# DDR3_Power_Termination.net
KiCad netlist of a schematic drawn in Altium Designer
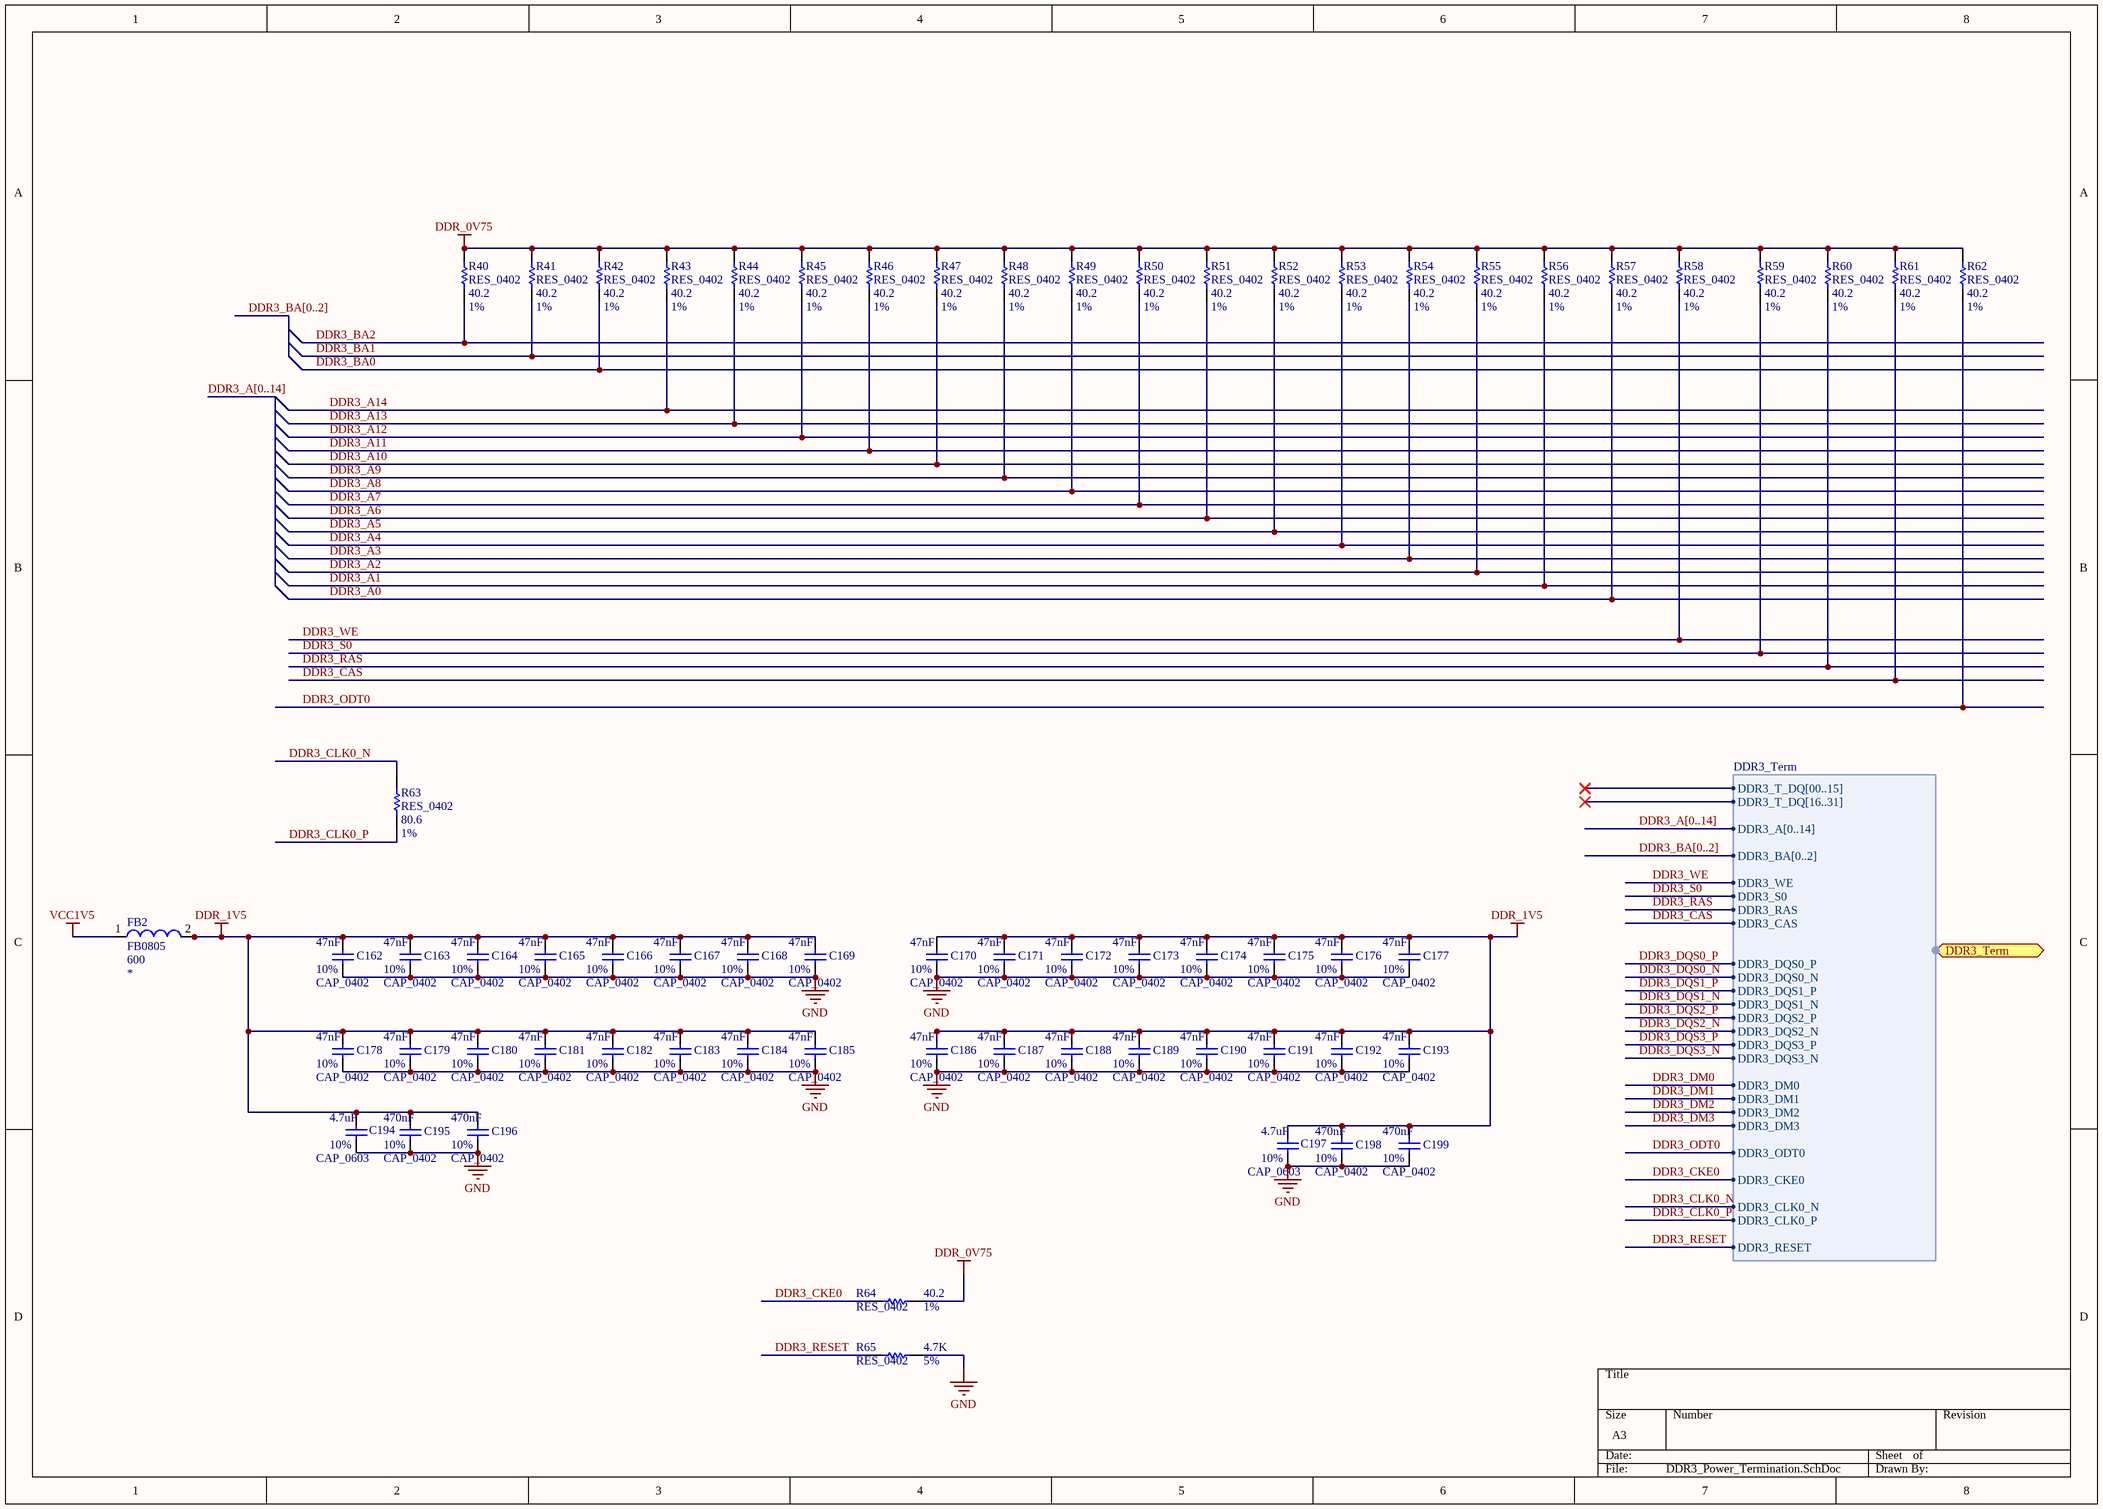
[diagram p0: DDR3_Power_Termination.SchDoc]

(export (version "E")
  (design (tool "Eeschema 10.0.6"))
  (components
    (comp (ref "C162")
      (value "CAP_0402")
      (footprint "CAPC0402(1005)60_N:CAPC0402(1005)60_N")
      (description "0.047uF, ceramic, 10% 6.3V X5R, 0402")
      (fields
        (field (name "ALTIUM_VALUE") "47nF")
        (field (name "TOLERANCE") "10%")
        (field (name "PART NUMBER") "GRM155R60J473KA01D")
        (field (name "MANUFACTURER") "Murata Electronics North America")
      )
      (libsource (lib "COMRAD_Database") (part "CAP_0402"))
    )
    (comp (ref "C163")
      (value "CAP_0402")
      (footprint "CAPC0402(1005)60_N:CAPC0402(1005)60_N")
      (description "0.047uF, ceramic, 10% 6.3V X5R, 0402")
      (fields
        (field (name "ALTIUM_VALUE") "47nF")
        (field (name "TOLERANCE") "10%")
        (field (name "PART NUMBER") "GRM155R60J473KA01D")
        (field (name "MANUFACTURER") "Murata Electronics North America")
      )
      (libsource (lib "COMRAD_Database") (part "CAP_0402"))
    )
    (comp (ref "C164")
      (value "CAP_0402")
      (footprint "CAPC0402(1005)60_N:CAPC0402(1005)60_N")
      (description "0.047uF, ceramic, 10% 6.3V X5R, 0402")
      (fields
        (field (name "ALTIUM_VALUE") "47nF")
        (field (name "TOLERANCE") "10%")
        (field (name "PART NUMBER") "GRM155R60J473KA01D")
        (field (name "MANUFACTURER") "Murata Electronics North America")
      )
      (libsource (lib "COMRAD_Database") (part "CAP_0402"))
    )
    (comp (ref "C165")
      (value "CAP_0402")
      (footprint "CAPC0402(1005)60_N:CAPC0402(1005)60_N")
      (description "0.047uF, ceramic, 10% 6.3V X5R, 0402")
      (fields
        (field (name "ALTIUM_VALUE") "47nF")
        (field (name "TOLERANCE") "10%")
        (field (name "PART NUMBER") "GRM155R60J473KA01D")
        (field (name "MANUFACTURER") "Murata Electronics North America")
      )
      (libsource (lib "COMRAD_Database") (part "CAP_0402"))
    )
    (comp (ref "C166")
      (value "CAP_0402")
      (footprint "CAPC0402(1005)60_N:CAPC0402(1005)60_N")
      (description "0.047uF, ceramic, 10% 6.3V X5R, 0402")
      (fields
        (field (name "ALTIUM_VALUE") "47nF")
        (field (name "TOLERANCE") "10%")
        (field (name "PART NUMBER") "GRM155R60J473KA01D")
        (field (name "MANUFACTURER") "Murata Electronics North America")
      )
      (libsource (lib "COMRAD_Database") (part "CAP_0402"))
    )
    (comp (ref "C167")
      (value "CAP_0402")
      (footprint "CAPC0402(1005)60_N:CAPC0402(1005)60_N")
      (description "0.047uF, ceramic, 10% 6.3V X5R, 0402")
      (fields
        (field (name "ALTIUM_VALUE") "47nF")
        (field (name "TOLERANCE") "10%")
        (field (name "PART NUMBER") "GRM155R60J473KA01D")
        (field (name "MANUFACTURER") "Murata Electronics North America")
      )
      (libsource (lib "COMRAD_Database") (part "CAP_0402"))
    )
    (comp (ref "C168")
      (value "CAP_0402")
      (footprint "CAPC0402(1005)60_N:CAPC0402(1005)60_N")
      (description "0.047uF, ceramic, 10% 6.3V X5R, 0402")
      (fields
        (field (name "ALTIUM_VALUE") "47nF")
        (field (name "TOLERANCE") "10%")
        (field (name "PART NUMBER") "GRM155R60J473KA01D")
        (field (name "MANUFACTURER") "Murata Electronics North America")
      )
      (libsource (lib "COMRAD_Database") (part "CAP_0402"))
    )
    (comp (ref "C169")
      (value "CAP_0402")
      (footprint "CAPC0402(1005)60_N:CAPC0402(1005)60_N")
      (description "0.047uF, ceramic, 10% 6.3V X5R, 0402")
      (fields
        (field (name "ALTIUM_VALUE") "47nF")
        (field (name "TOLERANCE") "10%")
        (field (name "PART NUMBER") "GRM155R60J473KA01D")
        (field (name "MANUFACTURER") "Murata Electronics North America")
      )
      (libsource (lib "COMRAD_Database") (part "CAP_0402"))
    )
    (comp (ref "C170")
      (value "CAP_0402")
      (footprint "CAPC0402(1005)60_N:CAPC0402(1005)60_N")
      (description "0.047uF, ceramic, 10% 6.3V X5R, 0402")
      (fields
        (field (name "ALTIUM_VALUE") "47nF")
        (field (name "TOLERANCE") "10%")
        (field (name "PART NUMBER") "GRM155R60J473KA01D")
        (field (name "MANUFACTURER") "Murata Electronics North America")
      )
      (libsource (lib "COMRAD_Database") (part "CAP_0402"))
    )
    (comp (ref "C171")
      (value "CAP_0402")
      (footprint "CAPC0402(1005)60_N:CAPC0402(1005)60_N")
      (description "0.047uF, ceramic, 10% 6.3V X5R, 0402")
      (fields
        (field (name "ALTIUM_VALUE") "47nF")
        (field (name "TOLERANCE") "10%")
        (field (name "PART NUMBER") "GRM155R60J473KA01D")
        (field (name "MANUFACTURER") "Murata Electronics North America")
      )
      (libsource (lib "COMRAD_Database") (part "CAP_0402"))
    )
    (comp (ref "C172")
      (value "CAP_0402")
      (footprint "CAPC0402(1005)60_N:CAPC0402(1005)60_N")
      (description "0.047uF, ceramic, 10% 6.3V X5R, 0402")
      (fields
        (field (name "ALTIUM_VALUE") "47nF")
        (field (name "TOLERANCE") "10%")
        (field (name "PART NUMBER") "GRM155R60J473KA01D")
        (field (name "MANUFACTURER") "Murata Electronics North America")
      )
      (libsource (lib "COMRAD_Database") (part "CAP_0402"))
    )
    (comp (ref "C173")
      (value "CAP_0402")
      (footprint "CAPC0402(1005)60_N:CAPC0402(1005)60_N")
      (description "0.047uF, ceramic, 10% 6.3V X5R, 0402")
      (fields
        (field (name "ALTIUM_VALUE") "47nF")
        (field (name "TOLERANCE") "10%")
        (field (name "PART NUMBER") "GRM155R60J473KA01D")
        (field (name "MANUFACTURER") "Murata Electronics North America")
      )
      (libsource (lib "COMRAD_Database") (part "CAP_0402"))
    )
    (comp (ref "C174")
      (value "CAP_0402")
      (footprint "CAPC0402(1005)60_N:CAPC0402(1005)60_N")
      (description "0.047uF, ceramic, 10% 6.3V X5R, 0402")
      (fields
        (field (name "ALTIUM_VALUE") "47nF")
        (field (name "TOLERANCE") "10%")
        (field (name "PART NUMBER") "GRM155R60J473KA01D")
        (field (name "MANUFACTURER") "Murata Electronics North America")
      )
      (libsource (lib "COMRAD_Database") (part "CAP_0402"))
    )
    (comp (ref "C175")
      (value "CAP_0402")
      (footprint "CAPC0402(1005)60_N:CAPC0402(1005)60_N")
      (description "0.047uF, ceramic, 10% 6.3V X5R, 0402")
      (fields
        (field (name "ALTIUM_VALUE") "47nF")
        (field (name "TOLERANCE") "10%")
        (field (name "PART NUMBER") "GRM155R60J473KA01D")
        (field (name "MANUFACTURER") "Murata Electronics North America")
      )
      (libsource (lib "COMRAD_Database") (part "CAP_0402"))
    )
    (comp (ref "C176")
      (value "CAP_0402")
      (footprint "CAPC0402(1005)60_N:CAPC0402(1005)60_N")
      (description "0.047uF, ceramic, 10% 6.3V X5R, 0402")
      (fields
        (field (name "ALTIUM_VALUE") "47nF")
        (field (name "TOLERANCE") "10%")
        (field (name "PART NUMBER") "GRM155R60J473KA01D")
        (field (name "MANUFACTURER") "Murata Electronics North America")
      )
      (libsource (lib "COMRAD_Database") (part "CAP_0402"))
    )
    (comp (ref "C177")
      (value "CAP_0402")
      (footprint "CAPC0402(1005)60_N:CAPC0402(1005)60_N")
      (description "0.047uF, ceramic, 10% 6.3V X5R, 0402")
      (fields
        (field (name "ALTIUM_VALUE") "47nF")
        (field (name "TOLERANCE") "10%")
        (field (name "PART NUMBER") "GRM155R60J473KA01D")
        (field (name "MANUFACTURER") "Murata Electronics North America")
      )
      (libsource (lib "COMRAD_Database") (part "CAP_0402"))
    )
    (comp (ref "C178")
      (value "CAP_0402")
      (footprint "CAPC0402(1005)60_N:CAPC0402(1005)60_N")
      (description "0.047uF, ceramic, 10% 6.3V X5R, 0402")
      (fields
        (field (name "ALTIUM_VALUE") "47nF")
        (field (name "TOLERANCE") "10%")
        (field (name "PART NUMBER") "GRM155R60J473KA01D")
        (field (name "MANUFACTURER") "Murata Electronics North America")
      )
      (libsource (lib "COMRAD_Database") (part "CAP_0402"))
    )
    (comp (ref "C179")
      (value "CAP_0402")
      (footprint "CAPC0402(1005)60_N:CAPC0402(1005)60_N")
      (description "0.047uF, ceramic, 10% 6.3V X5R, 0402")
      (fields
        (field (name "ALTIUM_VALUE") "47nF")
        (field (name "TOLERANCE") "10%")
        (field (name "PART NUMBER") "GRM155R60J473KA01D")
        (field (name "MANUFACTURER") "Murata Electronics North America")
      )
      (libsource (lib "COMRAD_Database") (part "CAP_0402"))
    )
    (comp (ref "C180")
      (value "CAP_0402")
      (footprint "CAPC0402(1005)60_N:CAPC0402(1005)60_N")
      (description "0.047uF, ceramic, 10% 6.3V X5R, 0402")
      (fields
        (field (name "ALTIUM_VALUE") "47nF")
        (field (name "TOLERANCE") "10%")
        (field (name "PART NUMBER") "GRM155R60J473KA01D")
        (field (name "MANUFACTURER") "Murata Electronics North America")
      )
      (libsource (lib "COMRAD_Database") (part "CAP_0402"))
    )
    (comp (ref "C181")
      (value "CAP_0402")
      (footprint "CAPC0402(1005)60_N:CAPC0402(1005)60_N")
      (description "0.047uF, ceramic, 10% 6.3V X5R, 0402")
      (fields
        (field (name "ALTIUM_VALUE") "47nF")
        (field (name "TOLERANCE") "10%")
        (field (name "PART NUMBER") "GRM155R60J473KA01D")
        (field (name "MANUFACTURER") "Murata Electronics North America")
      )
      (libsource (lib "COMRAD_Database") (part "CAP_0402"))
    )
    (comp (ref "C182")
      (value "CAP_0402")
      (footprint "CAPC0402(1005)60_N:CAPC0402(1005)60_N")
      (description "0.047uF, ceramic, 10% 6.3V X5R, 0402")
      (fields
        (field (name "ALTIUM_VALUE") "47nF")
        (field (name "TOLERANCE") "10%")
        (field (name "PART NUMBER") "GRM155R60J473KA01D")
        (field (name "MANUFACTURER") "Murata Electronics North America")
      )
      (libsource (lib "COMRAD_Database") (part "CAP_0402"))
    )
    (comp (ref "C183")
      (value "CAP_0402")
      (footprint "CAPC0402(1005)60_N:CAPC0402(1005)60_N")
      (description "0.047uF, ceramic, 10% 6.3V X5R, 0402")
      (fields
        (field (name "ALTIUM_VALUE") "47nF")
        (field (name "TOLERANCE") "10%")
        (field (name "PART NUMBER") "GRM155R60J473KA01D")
        (field (name "MANUFACTURER") "Murata Electronics North America")
      )
      (libsource (lib "COMRAD_Database") (part "CAP_0402"))
    )
    (comp (ref "C184")
      (value "CAP_0402")
      (footprint "CAPC0402(1005)60_N:CAPC0402(1005)60_N")
      (description "0.047uF, ceramic, 10% 6.3V X5R, 0402")
      (fields
        (field (name "ALTIUM_VALUE") "47nF")
        (field (name "TOLERANCE") "10%")
        (field (name "PART NUMBER") "GRM155R60J473KA01D")
        (field (name "MANUFACTURER") "Murata Electronics North America")
      )
      (libsource (lib "COMRAD_Database") (part "CAP_0402"))
    )
    (comp (ref "C185")
      (value "CAP_0402")
      (footprint "CAPC0402(1005)60_N:CAPC0402(1005)60_N")
      (description "0.047uF, ceramic, 10% 6.3V X5R, 0402")
      (fields
        (field (name "ALTIUM_VALUE") "47nF")
        (field (name "TOLERANCE") "10%")
        (field (name "PART NUMBER") "GRM155R60J473KA01D")
        (field (name "MANUFACTURER") "Murata Electronics North America")
      )
      (libsource (lib "COMRAD_Database") (part "CAP_0402"))
    )
    (comp (ref "C186")
      (value "CAP_0402")
      (footprint "CAPC0402(1005)60_N:CAPC0402(1005)60_N")
      (description "0.047uF, ceramic, 10% 6.3V X5R, 0402")
      (fields
        (field (name "ALTIUM_VALUE") "47nF")
        (field (name "TOLERANCE") "10%")
        (field (name "PART NUMBER") "GRM155R60J473KA01D")
        (field (name "MANUFACTURER") "Murata Electronics North America")
      )
      (libsource (lib "COMRAD_Database") (part "CAP_0402"))
    )
    (comp (ref "C187")
      (value "CAP_0402")
      (footprint "CAPC0402(1005)60_N:CAPC0402(1005)60_N")
      (description "0.047uF, ceramic, 10% 6.3V X5R, 0402")
      (fields
        (field (name "ALTIUM_VALUE") "47nF")
        (field (name "TOLERANCE") "10%")
        (field (name "PART NUMBER") "GRM155R60J473KA01D")
        (field (name "MANUFACTURER") "Murata Electronics North America")
      )
      (libsource (lib "COMRAD_Database") (part "CAP_0402"))
    )
    (comp (ref "C188")
      (value "CAP_0402")
      (footprint "CAPC0402(1005)60_N:CAPC0402(1005)60_N")
      (description "0.047uF, ceramic, 10% 6.3V X5R, 0402")
      (fields
        (field (name "ALTIUM_VALUE") "47nF")
        (field (name "TOLERANCE") "10%")
        (field (name "PART NUMBER") "GRM155R60J473KA01D")
        (field (name "MANUFACTURER") "Murata Electronics North America")
      )
      (libsource (lib "COMRAD_Database") (part "CAP_0402"))
    )
    (comp (ref "C189")
      (value "CAP_0402")
      (footprint "CAPC0402(1005)60_N:CAPC0402(1005)60_N")
      (description "0.047uF, ceramic, 10% 6.3V X5R, 0402")
      (fields
        (field (name "ALTIUM_VALUE") "47nF")
        (field (name "TOLERANCE") "10%")
        (field (name "PART NUMBER") "GRM155R60J473KA01D")
        (field (name "MANUFACTURER") "Murata Electronics North America")
      )
      (libsource (lib "COMRAD_Database") (part "CAP_0402"))
    )
    (comp (ref "C190")
      (value "CAP_0402")
      (footprint "CAPC0402(1005)60_N:CAPC0402(1005)60_N")
      (description "0.047uF, ceramic, 10% 6.3V X5R, 0402")
      (fields
        (field (name "ALTIUM_VALUE") "47nF")
        (field (name "TOLERANCE") "10%")
        (field (name "PART NUMBER") "GRM155R60J473KA01D")
        (field (name "MANUFACTURER") "Murata Electronics North America")
      )
      (libsource (lib "COMRAD_Database") (part "CAP_0402"))
    )
    (comp (ref "C191")
      (value "CAP_0402")
      (footprint "CAPC0402(1005)60_N:CAPC0402(1005)60_N")
      (description "0.047uF, ceramic, 10% 6.3V X5R, 0402")
      (fields
        (field (name "ALTIUM_VALUE") "47nF")
        (field (name "TOLERANCE") "10%")
        (field (name "PART NUMBER") "GRM155R60J473KA01D")
        (field (name "MANUFACTURER") "Murata Electronics North America")
      )
      (libsource (lib "COMRAD_Database") (part "CAP_0402"))
    )
    (comp (ref "C192")
      (value "CAP_0402")
      (footprint "CAPC0402(1005)60_N:CAPC0402(1005)60_N")
      (description "0.047uF, ceramic, 10% 6.3V X5R, 0402")
      (fields
        (field (name "ALTIUM_VALUE") "47nF")
        (field (name "TOLERANCE") "10%")
        (field (name "PART NUMBER") "GRM155R60J473KA01D")
        (field (name "MANUFACTURER") "Murata Electronics North America")
      )
      (libsource (lib "COMRAD_Database") (part "CAP_0402"))
    )
    (comp (ref "C193")
      (value "CAP_0402")
      (footprint "CAPC0402(1005)60_N:CAPC0402(1005)60_N")
      (description "0.047uF, ceramic, 10% 6.3V X5R, 0402")
      (fields
        (field (name "ALTIUM_VALUE") "47nF")
        (field (name "TOLERANCE") "10%")
        (field (name "PART NUMBER") "GRM155R60J473KA01D")
        (field (name "MANUFACTURER") "Murata Electronics North America")
      )
      (libsource (lib "COMRAD_Database") (part "CAP_0402"))
    )
    (comp (ref "C194")
      (value "CAP_0603")
      (footprint "CAPC0603(1608)100_N:CAPC0603(1608)100_N")
      (description "4.7uF, ceramic, 10% 6.3V X5R Low ESR, 0603")
      (fields
        (field (name "ALTIUM_VALUE") "4.7uF")
        (field (name "TOLERANCE") "10%")
        (field (name "PART NUMBER") "GRM188R60J475KE19D")
        (field (name "MANUFACTURER") "Murata Electronics North America")
      )
      (libsource (lib "COMRAD_Database") (part "CAP_0603"))
    )
    (comp (ref "C195")
      (value "CAP_0402")
      (footprint "CAPC0402(1005)60_N:CAPC0402(1005)60_N")
      (description "0.47uF, ceramic, 10% 6.3V X5R, 0402")
      (fields
        (field (name "ALTIUM_VALUE") "470nF")
        (field (name "TOLERANCE") "10%")
        (field (name "PART NUMBER") "GRM155R60J474KE19D")
        (field (name "MANUFACTURER") "Murata Electronics North America")
      )
      (libsource (lib "COMRAD_Database") (part "CAP_0402"))
    )
    (comp (ref "C196")
      (value "CAP_0402")
      (footprint "CAPC0402(1005)60_N:CAPC0402(1005)60_N")
      (description "0.47uF, ceramic, 10% 6.3V X5R, 0402")
      (fields
        (field (name "ALTIUM_VALUE") "470nF")
        (field (name "TOLERANCE") "10%")
        (field (name "PART NUMBER") "GRM155R60J474KE19D")
        (field (name "MANUFACTURER") "Murata Electronics North America")
      )
      (libsource (lib "COMRAD_Database") (part "CAP_0402"))
    )
    (comp (ref "C197")
      (value "CAP_0603")
      (footprint "CAPC0603(1608)100_N:CAPC0603(1608)100_N")
      (description "4.7uF, ceramic, 10% 6.3V X5R Low ESR, 0603")
      (fields
        (field (name "ALTIUM_VALUE") "4.7uF")
        (field (name "TOLERANCE") "10%")
        (field (name "PART NUMBER") "GRM188R60J475KE19D")
        (field (name "MANUFACTURER") "Murata Electronics North America")
      )
      (libsource (lib "COMRAD_Database") (part "CAP_0603"))
    )
    (comp (ref "C198")
      (value "CAP_0402")
      (footprint "CAPC0402(1005)60_N:CAPC0402(1005)60_N")
      (description "0.47uF, ceramic, 10% 6.3V X5R, 0402")
      (fields
        (field (name "ALTIUM_VALUE") "470nF")
        (field (name "TOLERANCE") "10%")
        (field (name "PART NUMBER") "GRM155R60J474KE19D")
        (field (name "MANUFACTURER") "Murata Electronics North America")
      )
      (libsource (lib "COMRAD_Database") (part "CAP_0402"))
    )
    (comp (ref "C199")
      (value "CAP_0402")
      (footprint "CAPC0402(1005)60_N:CAPC0402(1005)60_N")
      (description "0.47uF, ceramic, 10% 6.3V X5R, 0402")
      (fields
        (field (name "ALTIUM_VALUE") "470nF")
        (field (name "TOLERANCE") "10%")
        (field (name "PART NUMBER") "GRM155R60J474KE19D")
        (field (name "MANUFACTURER") "Murata Electronics North America")
      )
      (libsource (lib "COMRAD_Database") (part "CAP_0402"))
    )
    (comp (ref "FB2")
      (value "FB0805")
      (footprint "Inductor0805(2012)")
      (description "MPZ2012S601A, 600 ohm, 100MHz, 0805")
      (fields
        (field (name "RESISTANCE") "600")
        (field (name "MAX_CURRENT") "*")
        (field (name "PART NUMBER") "MPZ2012S601A")
        (field (name "MANUFACTURER") "TDK Corporation")
      )
      (libsource (lib "COMRAD_Database") (part "FerriteBead0805"))
    )
    (comp (ref "R40")
      (value "RES_0402")
      (footprint "RESC0402(1005)_N:RESC0402(1005)_N")
      (description "40.2 ohm, 1% 1/16W, 0402")
      (fields
        (field (name "ALTIUM_VALUE") "40.2")
        (field (name "TOLERANCE") "1%")
        (field (name "PART NUMBER") "RMCF0402FT40R2")
        (field (name "MANUFACTURER") "Stackpole Electronics")
      )
      (libsource (lib "COMRAD_Database") (part "RES_0402"))
    )
    (comp (ref "R41")
      (value "RES_0402")
      (footprint "RESC0402(1005)_N:RESC0402(1005)_N")
      (description "40.2 ohm, 1% 1/16W, 0402")
      (fields
        (field (name "ALTIUM_VALUE") "40.2")
        (field (name "TOLERANCE") "1%")
        (field (name "PART NUMBER") "RMCF0402FT40R2")
        (field (name "MANUFACTURER") "Stackpole Electronics")
      )
      (libsource (lib "COMRAD_Database") (part "RES_0402"))
    )
    (comp (ref "R42")
      (value "RES_0402")
      (footprint "RESC0402(1005)_N:RESC0402(1005)_N")
      (description "40.2 ohm, 1% 1/16W, 0402")
      (fields
        (field (name "ALTIUM_VALUE") "40.2")
        (field (name "TOLERANCE") "1%")
        (field (name "PART NUMBER") "RMCF0402FT40R2")
        (field (name "MANUFACTURER") "Stackpole Electronics")
      )
      (libsource (lib "COMRAD_Database") (part "RES_0402"))
    )
    (comp (ref "R43")
      (value "RES_0402")
      (footprint "RESC0402(1005)_N:RESC0402(1005)_N")
      (description "40.2 ohm, 1% 1/16W, 0402")
      (fields
        (field (name "ALTIUM_VALUE") "40.2")
        (field (name "TOLERANCE") "1%")
        (field (name "PART NUMBER") "RMCF0402FT40R2")
        (field (name "MANUFACTURER") "Stackpole Electronics")
      )
      (libsource (lib "COMRAD_Database") (part "RES_0402"))
    )
    (comp (ref "R44")
      (value "RES_0402")
      (footprint "RESC0402(1005)_N:RESC0402(1005)_N")
      (description "40.2 ohm, 1% 1/16W, 0402")
      (fields
        (field (name "ALTIUM_VALUE") "40.2")
        (field (name "TOLERANCE") "1%")
        (field (name "PART NUMBER") "RMCF0402FT40R2")
        (field (name "MANUFACTURER") "Stackpole Electronics")
      )
      (libsource (lib "COMRAD_Database") (part "RES_0402"))
    )
    (comp (ref "R45")
      (value "RES_0402")
      (footprint "RESC0402(1005)_N:RESC0402(1005)_N")
      (description "40.2 ohm, 1% 1/16W, 0402")
      (fields
        (field (name "ALTIUM_VALUE") "40.2")
        (field (name "TOLERANCE") "1%")
        (field (name "PART NUMBER") "RMCF0402FT40R2")
        (field (name "MANUFACTURER") "Stackpole Electronics")
      )
      (libsource (lib "COMRAD_Database") (part "RES_0402"))
    )
    (comp (ref "R46")
      (value "RES_0402")
      (footprint "RESC0402(1005)_N:RESC0402(1005)_N")
      (description "40.2 ohm, 1% 1/16W, 0402")
      (fields
        (field (name "ALTIUM_VALUE") "40.2")
        (field (name "TOLERANCE") "1%")
        (field (name "PART NUMBER") "RMCF0402FT40R2")
        (field (name "MANUFACTURER") "Stackpole Electronics")
      )
      (libsource (lib "COMRAD_Database") (part "RES_0402"))
    )
    (comp (ref "R47")
      (value "RES_0402")
      (footprint "RESC0402(1005)_N:RESC0402(1005)_N")
      (description "40.2 ohm, 1% 1/16W, 0402")
      (fields
        (field (name "ALTIUM_VALUE") "40.2")
        (field (name "TOLERANCE") "1%")
        (field (name "PART NUMBER") "RMCF0402FT40R2")
        (field (name "MANUFACTURER") "Stackpole Electronics")
      )
      (libsource (lib "COMRAD_Database") (part "RES_0402"))
    )
    (comp (ref "R48")
      (value "RES_0402")
      (footprint "RESC0402(1005)_N:RESC0402(1005)_N")
      (description "40.2 ohm, 1% 1/16W, 0402")
      (fields
        (field (name "ALTIUM_VALUE") "40.2")
        (field (name "TOLERANCE") "1%")
        (field (name "PART NUMBER") "RMCF0402FT40R2")
        (field (name "MANUFACTURER") "Stackpole Electronics")
      )
      (libsource (lib "COMRAD_Database") (part "RES_0402"))
    )
    (comp (ref "R49")
      (value "RES_0402")
      (footprint "RESC0402(1005)_N:RESC0402(1005)_N")
      (description "40.2 ohm, 1% 1/16W, 0402")
      (fields
        (field (name "ALTIUM_VALUE") "40.2")
        (field (name "TOLERANCE") "1%")
        (field (name "PART NUMBER") "RMCF0402FT40R2")
        (field (name "MANUFACTURER") "Stackpole Electronics")
      )
      (libsource (lib "COMRAD_Database") (part "RES_0402"))
    )
    (comp (ref "R50")
      (value "RES_0402")
      (footprint "RESC0402(1005)_N:RESC0402(1005)_N")
      (description "40.2 ohm, 1% 1/16W, 0402")
      (fields
        (field (name "ALTIUM_VALUE") "40.2")
        (field (name "TOLERANCE") "1%")
        (field (name "PART NUMBER") "RMCF0402FT40R2")
        (field (name "MANUFACTURER") "Stackpole Electronics")
      )
      (libsource (lib "COMRAD_Database") (part "RES_0402"))
    )
    (comp (ref "R51")
      (value "RES_0402")
      (footprint "RESC0402(1005)_N:RESC0402(1005)_N")
      (description "40.2 ohm, 1% 1/16W, 0402")
      (fields
        (field (name "ALTIUM_VALUE") "40.2")
        (field (name "TOLERANCE") "1%")
        (field (name "PART NUMBER") "RMCF0402FT40R2")
        (field (name "MANUFACTURER") "Stackpole Electronics")
      )
      (libsource (lib "COMRAD_Database") (part "RES_0402"))
    )
    (comp (ref "R52")
      (value "RES_0402")
      (footprint "RESC0402(1005)_N:RESC0402(1005)_N")
      (description "40.2 ohm, 1% 1/16W, 0402")
      (fields
        (field (name "ALTIUM_VALUE") "40.2")
        (field (name "TOLERANCE") "1%")
        (field (name "PART NUMBER") "RMCF0402FT40R2")
        (field (name "MANUFACTURER") "Stackpole Electronics")
      )
      (libsource (lib "COMRAD_Database") (part "RES_0402"))
    )
    (comp (ref "R53")
      (value "RES_0402")
      (footprint "RESC0402(1005)_N:RESC0402(1005)_N")
      (description "40.2 ohm, 1% 1/16W, 0402")
      (fields
        (field (name "ALTIUM_VALUE") "40.2")
        (field (name "TOLERANCE") "1%")
        (field (name "PART NUMBER") "RMCF0402FT40R2")
        (field (name "MANUFACTURER") "Stackpole Electronics")
      )
      (libsource (lib "COMRAD_Database") (part "RES_0402"))
    )
    (comp (ref "R54")
      (value "RES_0402")
      (footprint "RESC0402(1005)_N:RESC0402(1005)_N")
      (description "40.2 ohm, 1% 1/16W, 0402")
      (fields
        (field (name "ALTIUM_VALUE") "40.2")
        (field (name "TOLERANCE") "1%")
        (field (name "PART NUMBER") "RMCF0402FT40R2")
        (field (name "MANUFACTURER") "Stackpole Electronics")
      )
      (libsource (lib "COMRAD_Database") (part "RES_0402"))
    )
    (comp (ref "R55")
      (value "RES_0402")
      (footprint "RESC0402(1005)_N:RESC0402(1005)_N")
      (description "40.2 ohm, 1% 1/16W, 0402")
      (fields
        (field (name "ALTIUM_VALUE") "40.2")
        (field (name "TOLERANCE") "1%")
        (field (name "PART NUMBER") "RMCF0402FT40R2")
        (field (name "MANUFACTURER") "Stackpole Electronics")
      )
      (libsource (lib "COMRAD_Database") (part "RES_0402"))
    )
    (comp (ref "R56")
      (value "RES_0402")
      (footprint "RESC0402(1005)_N:RESC0402(1005)_N")
      (description "40.2 ohm, 1% 1/16W, 0402")
      (fields
        (field (name "ALTIUM_VALUE") "40.2")
        (field (name "TOLERANCE") "1%")
        (field (name "PART NUMBER") "RMCF0402FT40R2")
        (field (name "MANUFACTURER") "Stackpole Electronics")
      )
      (libsource (lib "COMRAD_Database") (part "RES_0402"))
    )
    (comp (ref "R57")
      (value "RES_0402")
      (footprint "RESC0402(1005)_N:RESC0402(1005)_N")
      (description "40.2 ohm, 1% 1/16W, 0402")
      (fields
        (field (name "ALTIUM_VALUE") "40.2")
        (field (name "TOLERANCE") "1%")
        (field (name "PART NUMBER") "RMCF0402FT40R2")
        (field (name "MANUFACTURER") "Stackpole Electronics")
      )
      (libsource (lib "COMRAD_Database") (part "RES_0402"))
    )
    (comp (ref "R58")
      (value "RES_0402")
      (footprint "RESC0402(1005)_N:RESC0402(1005)_N")
      (description "40.2 ohm, 1% 1/16W, 0402")
      (fields
        (field (name "ALTIUM_VALUE") "40.2")
        (field (name "TOLERANCE") "1%")
        (field (name "PART NUMBER") "RMCF0402FT40R2")
        (field (name "MANUFACTURER") "Stackpole Electronics")
      )
      (libsource (lib "COMRAD_Database") (part "RES_0402"))
    )
    (comp (ref "R59")
      (value "RES_0402")
      (footprint "RESC0402(1005)_N:RESC0402(1005)_N")
      (description "40.2 ohm, 1% 1/16W, 0402")
      (fields
        (field (name "ALTIUM_VALUE") "40.2")
        (field (name "TOLERANCE") "1%")
        (field (name "PART NUMBER") "RMCF0402FT40R2")
        (field (name "MANUFACTURER") "Stackpole Electronics")
      )
      (libsource (lib "COMRAD_Database") (part "RES_0402"))
    )
    (comp (ref "R60")
      (value "RES_0402")
      (footprint "RESC0402(1005)_N:RESC0402(1005)_N")
      (description "40.2 ohm, 1% 1/16W, 0402")
      (fields
        (field (name "ALTIUM_VALUE") "40.2")
        (field (name "TOLERANCE") "1%")
        (field (name "PART NUMBER") "RMCF0402FT40R2")
        (field (name "MANUFACTURER") "Stackpole Electronics")
      )
      (libsource (lib "COMRAD_Database") (part "RES_0402"))
    )
    (comp (ref "R61")
      (value "RES_0402")
      (footprint "RESC0402(1005)_N:RESC0402(1005)_N")
      (description "40.2 ohm, 1% 1/16W, 0402")
      (fields
        (field (name "ALTIUM_VALUE") "40.2")
        (field (name "TOLERANCE") "1%")
        (field (name "PART NUMBER") "RMCF0402FT40R2")
        (field (name "MANUFACTURER") "Stackpole Electronics")
      )
      (libsource (lib "COMRAD_Database") (part "RES_0402"))
    )
    (comp (ref "R62")
      (value "RES_0402")
      (footprint "RESC0402(1005)_N:RESC0402(1005)_N")
      (description "40.2 ohm, 1% 1/16W, 0402")
      (fields
        (field (name "ALTIUM_VALUE") "40.2")
        (field (name "TOLERANCE") "1%")
        (field (name "PART NUMBER") "RMCF0402FT40R2")
        (field (name "MANUFACTURER") "Stackpole Electronics")
      )
      (libsource (lib "COMRAD_Database") (part "RES_0402"))
    )
    (comp (ref "R63")
      (value "RES_0402")
      (footprint "RESC0402(1005)_N:RESC0402(1005)_N")
      (description "80.6 ohm, 1% 1/16W, 0402")
      (fields
        (field (name "ALTIUM_VALUE") "80.6")
        (field (name "TOLERANCE") "1%")
        (field (name "PART NUMBER") "RMCF0402FT80R6")
        (field (name "MANUFACTURER") "Stackpole Electronics")
      )
      (libsource (lib "COMRAD_Database") (part "RES_0402"))
    )
    (comp (ref "R64")
      (value "RES_0402")
      (footprint "RESC0402(1005)_N:RESC0402(1005)_N")
      (description "40.2 ohm, 1% 1/16W, 0402")
      (fields
        (field (name "ALTIUM_VALUE") "40.2")
        (field (name "TOLERANCE") "1%")
        (field (name "PART NUMBER") "RMCF0402FT40R2")
        (field (name "MANUFACTURER") "Stackpole Electronics")
      )
      (libsource (lib "COMRAD_Database") (part "RES_0402"))
    )
    (comp (ref "R65")
      (value "RES_0402")
      (footprint "RESC0402(1005)_N:RESC0402(1005)_N")
      (description "4.7K ohm, 5%, 1/16W, 0402")
      (fields
        (field (name "ALTIUM_VALUE") "4.7K")
        (field (name "TOLERANCE") "5%")
        (field (name "PART NUMBER") "RC0402JR-074K7L")
        (field (name "MANUFACTURER") "Yageo America")
      )
      (libsource (lib "COMRAD_Database") (part "RES_0402"))
    )
  )
  (nets
    (net (code "3") (name "/DDR3_A0") (class "Default")
      (node (ref "R57") (pin "1") (pinfunction "1_1") (pintype "passive"))
    )
    (net (code "4") (name "/DDR3_A1") (class "Default")
      (node (ref "R56") (pin "1") (pinfunction "1_1") (pintype "passive"))
    )
    (net (code "5") (name "/DDR3_A2") (class "Default")
      (node (ref "R55") (pin "1") (pinfunction "1_1") (pintype "passive"))
    )
    (net (code "6") (name "/DDR3_A3") (class "Default")
      (node (ref "R54") (pin "1") (pinfunction "1_1") (pintype "passive"))
    )
    (net (code "7") (name "/DDR3_A4") (class "Default")
      (node (ref "R53") (pin "1") (pinfunction "1_1") (pintype "passive"))
    )
    (net (code "8") (name "/DDR3_A5") (class "Default")
      (node (ref "R52") (pin "1") (pinfunction "1_1") (pintype "passive"))
    )
    (net (code "9") (name "/DDR3_A6") (class "Default")
      (node (ref "R51") (pin "1") (pinfunction "1_1") (pintype "passive"))
    )
    (net (code "10") (name "/DDR3_A7") (class "Default")
      (node (ref "R50") (pin "1") (pinfunction "1_1") (pintype "passive"))
    )
    (net (code "11") (name "/DDR3_A8") (class "Default")
      (node (ref "R49") (pin "1") (pinfunction "1_1") (pintype "passive"))
    )
    (net (code "12") (name "/DDR3_A9") (class "Default")
      (node (ref "R48") (pin "1") (pinfunction "1_1") (pintype "passive"))
    )
    (net (code "13") (name "/DDR3_A10") (class "Default")
      (node (ref "R47") (pin "1") (pinfunction "1_1") (pintype "passive"))
    )
    (net (code "14") (name "/DDR3_A11") (class "Default")
      (node (ref "R46") (pin "1") (pinfunction "1_1") (pintype "passive"))
    )
    (net (code "15") (name "/DDR3_A12") (class "Default")
      (node (ref "R45") (pin "1") (pinfunction "1_1") (pintype "passive"))
    )
    (net (code "16") (name "/DDR3_A13") (class "Default")
      (node (ref "R44") (pin "1") (pinfunction "1_1") (pintype "passive"))
    )
    (net (code "17") (name "/DDR3_A14") (class "Default")
      (node (ref "R43") (pin "1") (pinfunction "1_1") (pintype "passive"))
    )
    (net (code "19") (name "/DDR3_BA0") (class "Default")
      (node (ref "R42") (pin "1") (pinfunction "1_1") (pintype "passive"))
    )
    (net (code "20") (name "/DDR3_BA1") (class "Default")
      (node (ref "R41") (pin "1") (pinfunction "1_1") (pintype "passive"))
    )
    (net (code "21") (name "/DDR3_BA2") (class "Default")
      (node (ref "R40") (pin "1") (pinfunction "1_1") (pintype "passive"))
    )
    (net (code "23") (name "/DDR3_CAS") (class "Default")
      (node (ref "R61") (pin "1") (pinfunction "1_1") (pintype "passive"))
    )
    (net (code "24") (name "/DDR3_CKE0") (class "Default")
      (node (ref "R64") (pin "1") (pinfunction "1_1") (pintype "passive"))
    )
    (net (code "25") (name "/DDR3_CLK0_N") (class "Default")
      (node (ref "R63") (pin "2") (pinfunction "2_2") (pintype "passive"))
    )
    (net (code "26") (name "/DDR3_CLK0_P") (class "Default")
      (node (ref "R63") (pin "1") (pinfunction "1_1") (pintype "passive"))
    )
    (net (code "39") (name "/DDR3_ODT0") (class "Default")
      (node (ref "R62") (pin "1") (pinfunction "1_1") (pintype "passive"))
    )
    (net (code "40") (name "/DDR3_RAS") (class "Default")
      (node (ref "R60") (pin "1") (pinfunction "1_1") (pintype "passive"))
    )
    (net (code "41") (name "/DDR3_RESET") (class "Default")
      (node (ref "R65") (pin "1") (pinfunction "1_1") (pintype "passive"))
    )
    (net (code "42") (name "/DDR3_S0") (class "Default")
      (node (ref "R59") (pin "1") (pinfunction "1_1") (pintype "passive"))
    )
    (net (code "44") (name "/DDR3_WE") (class "Default")
      (node (ref "R58") (pin "1") (pinfunction "1_1") (pintype "passive"))
    )
    (net (code "46") (name "DDR_0V75") (class "Default")
      (node (ref "R40") (pin "2") (pinfunction "2_2") (pintype "passive"))
      (node (ref "R41") (pin "2") (pinfunction "2_2") (pintype "passive"))
      (node (ref "R42") (pin "2") (pinfunction "2_2") (pintype "passive"))
      (node (ref "R43") (pin "2") (pinfunction "2_2") (pintype "passive"))
      (node (ref "R44") (pin "2") (pinfunction "2_2") (pintype "passive"))
      (node (ref "R45") (pin "2") (pinfunction "2_2") (pintype "passive"))
      (node (ref "R46") (pin "2") (pinfunction "2_2") (pintype "passive"))
      (node (ref "R47") (pin "2") (pinfunction "2_2") (pintype "passive"))
      (node (ref "R48") (pin "2") (pinfunction "2_2") (pintype "passive"))
      (node (ref "R49") (pin "2") (pinfunction "2_2") (pintype "passive"))
      (node (ref "R50") (pin "2") (pinfunction "2_2") (pintype "passive"))
      (node (ref "R51") (pin "2") (pinfunction "2_2") (pintype "passive"))
      (node (ref "R52") (pin "2") (pinfunction "2_2") (pintype "passive"))
      (node (ref "R53") (pin "2") (pinfunction "2_2") (pintype "passive"))
      (node (ref "R54") (pin "2") (pinfunction "2_2") (pintype "passive"))
      (node (ref "R55") (pin "2") (pinfunction "2_2") (pintype "passive"))
      (node (ref "R56") (pin "2") (pinfunction "2_2") (pintype "passive"))
      (node (ref "R57") (pin "2") (pinfunction "2_2") (pintype "passive"))
      (node (ref "R58") (pin "2") (pinfunction "2_2") (pintype "passive"))
      (node (ref "R59") (pin "2") (pinfunction "2_2") (pintype "passive"))
      (node (ref "R60") (pin "2") (pinfunction "2_2") (pintype "passive"))
      (node (ref "R61") (pin "2") (pinfunction "2_2") (pintype "passive"))
      (node (ref "R62") (pin "2") (pinfunction "2_2") (pintype "passive"))
      (node (ref "R64") (pin "2") (pinfunction "2_2") (pintype "passive"))
    )
    (net (code "47") (name "DDR_1V5") (class "Default")
      (node (ref "C162") (pin "2") (pinfunction "2_2") (pintype "passive"))
      (node (ref "C163") (pin "2") (pinfunction "2_2") (pintype "passive"))
      (node (ref "C164") (pin "2") (pinfunction "2_2") (pintype "passive"))
      (node (ref "C165") (pin "2") (pinfunction "2_2") (pintype "passive"))
      (node (ref "C166") (pin "2") (pinfunction "2_2") (pintype "passive"))
      (node (ref "C167") (pin "2") (pinfunction "2_2") (pintype "passive"))
      (node (ref "C168") (pin "2") (pinfunction "2_2") (pintype "passive"))
      (node (ref "C169") (pin "2") (pinfunction "2_2") (pintype "passive"))
      (node (ref "C170") (pin "2") (pinfunction "2_2") (pintype "passive"))
      (node (ref "C171") (pin "2") (pinfunction "2_2") (pintype "passive"))
      (node (ref "C172") (pin "2") (pinfunction "2_2") (pintype "passive"))
      (node (ref "C173") (pin "2") (pinfunction "2_2") (pintype "passive"))
      (node (ref "C174") (pin "2") (pinfunction "2_2") (pintype "passive"))
      (node (ref "C175") (pin "2") (pinfunction "2_2") (pintype "passive"))
      (node (ref "C176") (pin "2") (pinfunction "2_2") (pintype "passive"))
      (node (ref "C177") (pin "2") (pinfunction "2_2") (pintype "passive"))
      (node (ref "C178") (pin "2") (pinfunction "2_2") (pintype "passive"))
      (node (ref "C179") (pin "2") (pinfunction "2_2") (pintype "passive"))
      (node (ref "C180") (pin "2") (pinfunction "2_2") (pintype "passive"))
      (node (ref "C181") (pin "2") (pinfunction "2_2") (pintype "passive"))
      (node (ref "C182") (pin "2") (pinfunction "2_2") (pintype "passive"))
      (node (ref "C183") (pin "2") (pinfunction "2_2") (pintype "passive"))
      (node (ref "C184") (pin "2") (pinfunction "2_2") (pintype "passive"))
      (node (ref "C185") (pin "2") (pinfunction "2_2") (pintype "passive"))
      (node (ref "C186") (pin "2") (pinfunction "2_2") (pintype "passive"))
      (node (ref "C187") (pin "2") (pinfunction "2_2") (pintype "passive"))
      (node (ref "C188") (pin "2") (pinfunction "2_2") (pintype "passive"))
      (node (ref "C189") (pin "2") (pinfunction "2_2") (pintype "passive"))
      (node (ref "C190") (pin "2") (pinfunction "2_2") (pintype "passive"))
      (node (ref "C191") (pin "2") (pinfunction "2_2") (pintype "passive"))
      (node (ref "C192") (pin "2") (pinfunction "2_2") (pintype "passive"))
      (node (ref "C193") (pin "2") (pinfunction "2_2") (pintype "passive"))
      (node (ref "C194") (pin "2") (pinfunction "2_2") (pintype "passive"))
      (node (ref "C195") (pin "2") (pinfunction "2_2") (pintype "passive"))
      (node (ref "C196") (pin "2") (pinfunction "2_2") (pintype "passive"))
      (node (ref "C197") (pin "2") (pinfunction "2_2") (pintype "passive"))
      (node (ref "C198") (pin "2") (pinfunction "2_2") (pintype "passive"))
      (node (ref "C199") (pin "2") (pinfunction "2_2") (pintype "passive"))
      (node (ref "FB2") (pin "2") (pinfunction "2_2") (pintype "passive"))
    )
    (net (code "48") (name "GND") (class "Default")
      (node (ref "C162") (pin "1") (pinfunction "1_1") (pintype "passive"))
      (node (ref "C163") (pin "1") (pinfunction "1_1") (pintype "passive"))
      (node (ref "C164") (pin "1") (pinfunction "1_1") (pintype "passive"))
      (node (ref "C165") (pin "1") (pinfunction "1_1") (pintype "passive"))
      (node (ref "C166") (pin "1") (pinfunction "1_1") (pintype "passive"))
      (node (ref "C167") (pin "1") (pinfunction "1_1") (pintype "passive"))
      (node (ref "C168") (pin "1") (pinfunction "1_1") (pintype "passive"))
      (node (ref "C169") (pin "1") (pinfunction "1_1") (pintype "passive"))
      (node (ref "C170") (pin "1") (pinfunction "1_1") (pintype "passive"))
      (node (ref "C171") (pin "1") (pinfunction "1_1") (pintype "passive"))
      (node (ref "C172") (pin "1") (pinfunction "1_1") (pintype "passive"))
      (node (ref "C173") (pin "1") (pinfunction "1_1") (pintype "passive"))
      (node (ref "C174") (pin "1") (pinfunction "1_1") (pintype "passive"))
      (node (ref "C175") (pin "1") (pinfunction "1_1") (pintype "passive"))
      (node (ref "C176") (pin "1") (pinfunction "1_1") (pintype "passive"))
      (node (ref "C177") (pin "1") (pinfunction "1_1") (pintype "passive"))
      (node (ref "C178") (pin "1") (pinfunction "1_1") (pintype "passive"))
      (node (ref "C179") (pin "1") (pinfunction "1_1") (pintype "passive"))
      (node (ref "C180") (pin "1") (pinfunction "1_1") (pintype "passive"))
      (node (ref "C181") (pin "1") (pinfunction "1_1") (pintype "passive"))
      (node (ref "C182") (pin "1") (pinfunction "1_1") (pintype "passive"))
      (node (ref "C183") (pin "1") (pinfunction "1_1") (pintype "passive"))
      (node (ref "C184") (pin "1") (pinfunction "1_1") (pintype "passive"))
      (node (ref "C185") (pin "1") (pinfunction "1_1") (pintype "passive"))
      (node (ref "C186") (pin "1") (pinfunction "1_1") (pintype "passive"))
      (node (ref "C187") (pin "1") (pinfunction "1_1") (pintype "passive"))
      (node (ref "C188") (pin "1") (pinfunction "1_1") (pintype "passive"))
      (node (ref "C189") (pin "1") (pinfunction "1_1") (pintype "passive"))
      (node (ref "C190") (pin "1") (pinfunction "1_1") (pintype "passive"))
      (node (ref "C191") (pin "1") (pinfunction "1_1") (pintype "passive"))
      (node (ref "C192") (pin "1") (pinfunction "1_1") (pintype "passive"))
      (node (ref "C193") (pin "1") (pinfunction "1_1") (pintype "passive"))
      (node (ref "C194") (pin "1") (pinfunction "1_1") (pintype "passive"))
      (node (ref "C195") (pin "1") (pinfunction "1_1") (pintype "passive"))
      (node (ref "C196") (pin "1") (pinfunction "1_1") (pintype "passive"))
      (node (ref "C197") (pin "1") (pinfunction "1_1") (pintype "passive"))
      (node (ref "C198") (pin "1") (pinfunction "1_1") (pintype "passive"))
      (node (ref "C199") (pin "1") (pinfunction "1_1") (pintype "passive"))
      (node (ref "R65") (pin "2") (pinfunction "2_2") (pintype "passive"))
    )
    (net (code "49") (name "VCC1V5") (class "Default")
      (node (ref "FB2") (pin "1") (pinfunction "1_1") (pintype "passive"))
    )
  )
)
